# BQ25750.net
KiCad netlist of a schematic drawn in Altium Designer
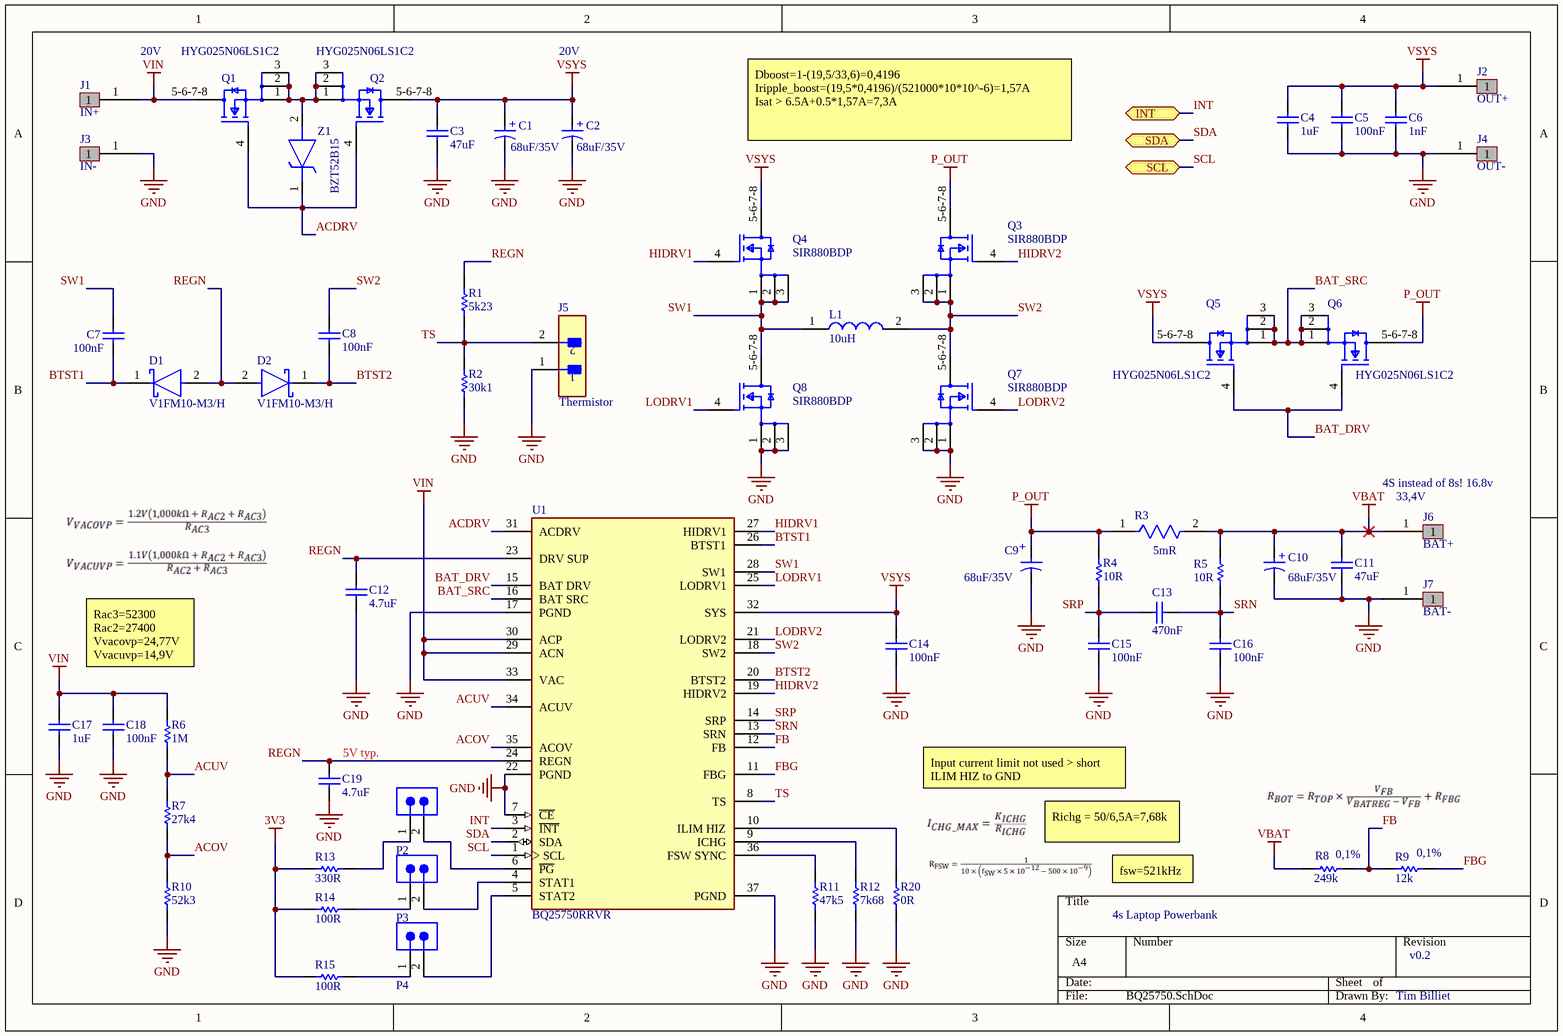
[diagram p0: BQ25750.SchDoc]

(export (version "E")
  (design (tool "Eeschema 10.0.6"))
  (components
    (comp (ref "C1")
      (value "68uF/35V")
      (footprint "Wurth D6.3x7.7mm")
      (fields (field (name "Comment") "Nichicon 68uF/35V Elco"))
      (libsource (lib "Passives") (part "Nichicon 68uF/35V Elco"))
    )
    (comp (ref "C2")
      (value "68uF/35V")
      (footprint "Wurth D6.3x7.7mm")
      (fields (field (name "Comment") "Nichicon 68uF/35V Elco"))
      (libsource (lib "Passives") (part "Nichicon 68uF/35V Elco"))
    )
    (comp (ref "C3")
      (value "47uF")
      (footprint "Wurth 1206 Capacitor")
      (fields (field (name "Comment") "Generic Capacitor 47uF 1206"))
      (libsource (lib "Passives") (part "Generic Capacitor 47uF 1206"))
    )
    (comp (ref "C4")
      (value "1uF")
      (footprint "Wurth 1206 Capacitor")
      (fields (field (name "Comment") "Generic Capacitor 1uF 1206"))
      (libsource (lib "Passives") (part "Generic Capacitor 1uF 1206"))
    )
    (comp (ref "C5")
      (value "100nF")
      (footprint "Wurth 0603 capacitor")
      (fields (field (name "Comment") "Generic Capacitor 100nF 0603"))
      (libsource (lib "Passives") (part "Generic Capacitor 100nF 0603"))
    )
    (comp (ref "C6")
      (value "1nF")
      (footprint "Wurth 0603 capacitor")
      (fields (field (name "Comment") "Generic Capacitor 1nF 0603"))
      (libsource (lib "Passives") (part "Generic Capacitor 1nF 0603"))
    )
    (comp (ref "C7")
      (value "100nF")
      (footprint "Wurth 0603 capacitor")
      (fields (field (name "Comment") "Generic Capacitor 100nF 0603"))
      (libsource (lib "Passives") (part "Generic Capacitor 100nF 0603"))
    )
    (comp (ref "C8")
      (value "100nF")
      (footprint "Wurth 0603 capacitor")
      (fields (field (name "Comment") "Generic Capacitor 100nF 0603"))
      (libsource (lib "Passives") (part "Generic Capacitor 100nF 0603"))
    )
    (comp (ref "C9")
      (value "68uF/35V")
      (footprint "Wurth D6.3x7.7mm")
      (fields (field (name "Comment") "Nichicon 68uF/35V Elco"))
      (libsource (lib "") (part "Nichicon 68uF/35V Elco_1"))
    )
    (comp (ref "C10")
      (value "68uF/35V")
      (footprint "Wurth D6.3x7.7mm")
      (fields (field (name "Comment") "Nichicon 68uF/35V Elco"))
      (libsource (lib "Passives") (part "Nichicon 68uF/35V Elco"))
    )
    (comp (ref "C11")
      (value "47uF")
      (footprint "Wurth 1206 Capacitor")
      (fields (field (name "Comment") "Generic Capacitor 47uF 1206"))
      (libsource (lib "Passives") (part "Generic Capacitor 47uF 1206"))
    )
    (comp (ref "C12")
      (value "4.7uF")
      (footprint "Wurth 0603 capacitor")
      (fields (field (name "Comment") "Generic Capacitor 4.7uF 0603"))
      (libsource (lib "Passives") (part "Generic Capacitor 4.7uF 0603"))
    )
    (comp (ref "C13")
      (value "470nF")
      (footprint "Wurth 0603 capacitor")
      (fields (field (name "Comment") "Generic Capacitor 470nF 0603"))
      (libsource (lib "Passives") (part "Generic Capacitor 470nF 0603"))
    )
    (comp (ref "C14")
      (value "100nF")
      (footprint "Wurth 0603 capacitor")
      (fields (field (name "Comment") "Generic Capacitor 100nF 0603"))
      (libsource (lib "Passives") (part "Generic Capacitor 100nF 0603"))
    )
    (comp (ref "C15")
      (value "100nF")
      (footprint "Wurth 0603 capacitor")
      (fields (field (name "Comment") "Generic Capacitor 100nF 0603"))
      (libsource (lib "Passives") (part "Generic Capacitor 100nF 0603"))
    )
    (comp (ref "C16")
      (value "100nF")
      (footprint "Wurth 0603 capacitor")
      (fields (field (name "Comment") "Generic Capacitor 100nF 0603"))
      (libsource (lib "Passives") (part "Generic Capacitor 100nF 0603"))
    )
    (comp (ref "C17")
      (value "1uF")
      (footprint "Wurth 0603 capacitor")
      (fields (field (name "Comment") "Generic Capacitor 1uF 0603"))
      (libsource (lib "Passives") (part "Generic Capacitor 1uF 0603"))
    )
    (comp (ref "C18")
      (value "100nF")
      (footprint "Wurth 0603 capacitor")
      (fields (field (name "Comment") "Generic Capacitor 100nF 0603"))
      (libsource (lib "Passives") (part "Generic Capacitor 100nF 0603"))
    )
    (comp (ref "C19")
      (value "4.7uF")
      (footprint "Wurth 0603 capacitor")
      (fields (field (name "Comment") "Generic Capacitor 4.7uF 0603"))
      (libsource (lib "Passives") (part "Generic Capacitor 4.7uF 0603"))
    )
    (comp (ref "D1")
      (value "V1FM10-M3/H")
      (footprint "FP-V1FM10-M3-H-MFG")
      (description "1A 100V SMF TRENCH SKY RECT")
      (libsource (lib "Altium Content Vault") (part "1d6ec82d83fb6aee721767c19dac4b9"))
    )
    (comp (ref "D2")
      (value "V1FM10-M3/H")
      (footprint "FP-V1FM10-M3-H-MFG")
      (description "1A 100V SMF TRENCH SKY RECT")
      (libsource (lib "Altium Content Vault") (part "1d6ec82d83fb6aee721767c19dac4b9"))
    )
    (comp (ref "J1") (value "IN+") (footprint "Solder Pad 3X4MM") (libsource (lib "") (part "Solder pad_1")))
    (comp (ref "J2")
      (value "OUT+")
      (footprint "Solder Pad 3X4MM")
      (libsource (lib "Connectors") (part "Solder pad"))
    )
    (comp (ref "J3") (value "IN-") (footprint "Solder Pad 3X4MM") (libsource (lib "") (part "Solder pad_1")))
    (comp (ref "J4")
      (value "OUT-")
      (footprint "Solder Pad 3X4MM")
      (libsource (lib "Connectors") (part "Solder pad"))
    )
    (comp (ref "J5")
      (value "B2B-PH-K(LF)(SN)")
      (footprint "FP-B2B-PH-K_LF_SN-MFG")
      (description "Connector Header Through Hole 2 position 0.079\" (2.00mm)")
      (libsource (lib "Altium Content Vault") (part "3bc925449376181038e59eaffc5286c"))
    )
    (comp (ref "J6")
      (value "BAT+")
      (footprint "Solder Pad 3X4MM")
      (libsource (lib "Connectors") (part "Solder pad"))
    )
    (comp (ref "J7")
      (value "BAT-")
      (footprint "Solder Pad 3X4MM")
      (libsource (lib "Connectors") (part "Solder pad"))
    )
    (comp (ref "L1")
      (value "10uH")
      (footprint "Cjiang 11.5x10mm inductor")
      (fields (field (name "Comment") "Cjiang Inductor 10uH 8A"))
      (libsource (lib "Passives") (part "Cjiang Inductor 10uH 8A"))
    )
    (comp (ref "P2")
      (value "61300211121")
      (footprint "2x1 2.54mm F")
      (description "WR-PHD Pin Header, THT, Vertical, pitch 2.54mm, 1 Row, 2P")
      (fields (field (name "MANUFACTURER") "Wurth Elektronik"))
      (libsource (lib "2.54mm_pin_headers") (part "2P"))
    )
    (comp (ref "P3")
      (value "61300211121")
      (footprint "2x1 2.54mm F")
      (description "WR-PHD Pin Header, THT, Vertical, pitch 2.54mm, 1 Row, 2P")
      (fields (field (name "MANUFACTURER") "Wurth Elektronik"))
      (libsource (lib "2.54mm_pin_headers") (part "2P"))
    )
    (comp (ref "P4")
      (value "61300211121")
      (footprint "2x1 2.54mm F")
      (description "WR-PHD Pin Header, THT, Vertical, pitch 2.54mm, 1 Row, 2P")
      (fields (field (name "MANUFACTURER") "Wurth Elektronik"))
      (libsource (lib "2.54mm_pin_headers") (part "2P"))
    )
    (comp (ref "Q1")
      (value "HYG025N06LS1C2")
      (footprint "Huayi PDFN8L")
      (description "MOSFET N-CH VDS = 60V,ID = 170A, VGS = 20V PDFN8L")
      (libsource (lib "N CHN FET") (part "Huayi HYG025N06LS1C2"))
    )
    (comp (ref "Q2")
      (value "HYG025N06LS1C2")
      (footprint "Huayi PDFN8L")
      (description "MOSFET N-CH VDS = 60V,ID = 170A, VGS = 20V PDFN8L")
      (libsource (lib "N CHN FET") (part "Huayi HYG025N06LS1C2"))
    )
    (comp (ref "Q3")
      (value "SIR880BDP")
      (footprint "Vishay PowerPAKSO-8")
      (description "Mosfet, N-Ch, 80V, 70.6A, 150Degc, 71.4W Rohs Compliant: Yes ¦Vishay SIR880BDP-T1-RE3")
      (fields
        (field (name "MANUFACTURER") "Vishay")
        (field (name "MANUFACTURER PART NUMBER") "SIR880BDP-T1-RE3")
      )
      (libsource (lib "N_CHN_FET") (part "Vishay SIR880BDP"))
    )
    (comp (ref "Q4")
      (value "SIR880BDP")
      (footprint "Vishay PowerPAKSO-8")
      (description "Mosfet, N-Ch, 80V, 70.6A, 150Degc, 71.4W Rohs Compliant: Yes ¦Vishay SIR880BDP-T1-RE3")
      (fields
        (field (name "MANUFACTURER") "Vishay")
        (field (name "MANUFACTURER PART NUMBER") "SIR880BDP-T1-RE3")
      )
      (libsource (lib "N_CHN_FET") (part "Vishay SIR880BDP"))
    )
    (comp (ref "Q5")
      (value "HYG025N06LS1C2")
      (footprint "Huayi PDFN8L")
      (description "MOSFET N-CH VDS = 60V,ID = 170A, VGS = 20V PDFN8L")
      (libsource (lib "N CHN FET") (part "Huayi HYG025N06LS1C2"))
    )
    (comp (ref "Q6")
      (value "HYG025N06LS1C2")
      (footprint "Huayi PDFN8L")
      (description "MOSFET N-CH VDS = 60V,ID = 170A, VGS = 20V PDFN8L")
      (libsource (lib "N CHN FET") (part "Huayi HYG025N06LS1C2"))
    )
    (comp (ref "Q7")
      (value "SIR880BDP")
      (footprint "Vishay PowerPAKSO-8")
      (description "Mosfet, N-Ch, 80V, 70.6A, 150Degc, 71.4W Rohs Compliant: Yes ¦Vishay SIR880BDP-T1-RE3")
      (fields
        (field (name "MANUFACTURER") "Vishay")
        (field (name "MANUFACTURER PART NUMBER") "SIR880BDP-T1-RE3")
      )
      (libsource (lib "N_CHN_FET") (part "Vishay SIR880BDP"))
    )
    (comp (ref "Q8")
      (value "SIR880BDP")
      (footprint "Vishay PowerPAKSO-8")
      (description "Mosfet, N-Ch, 80V, 70.6A, 150Degc, 71.4W Rohs Compliant: Yes ¦Vishay SIR880BDP-T1-RE3")
      (fields
        (field (name "MANUFACTURER") "Vishay")
        (field (name "MANUFACTURER PART NUMBER") "SIR880BDP-T1-RE3")
      )
      (libsource (lib "N_CHN_FET") (part "Vishay SIR880BDP"))
    )
    (comp (ref "R1")
      (value "5k23")
      (footprint "Wurth 0603 Resistor")
      (fields (field (name "Comment") "Generic Resistor 5k23 0603"))
      (libsource (lib "Passives") (part "Generic Resistor 5k23 0603"))
    )
    (comp (ref "R2")
      (value "30k1")
      (footprint "Wurth 0603 Resistor")
      (fields (field (name "Comment") "Generic Resistor 30k1 0603"))
      (libsource (lib "Passives") (part "Generic Resistor 30k1 0603"))
    )
    (comp (ref "R3")
      (value "ERJ-M1WSF5M0U")
      (footprint "FP-ERJM1WS-MFG")
      (description "RES 0.005 OHM 1% 1W 2512")
      (fields (field (name "RESISTANCE") "5mR") (field (name "TOLERANCE") "1%"))
      (libsource (lib "Altium Content Vault") (part "8db39607336c341a927600551d01821"))
    )
    (comp (ref "R4")
      (value "10R")
      (footprint "Wurth 0603 Resistor")
      (fields (field (name "Comment") "Generic Resistor 10R 0603"))
      (libsource (lib "Passives") (part "Generic Resistor 10R 0603"))
    )
    (comp (ref "R5")
      (value "10R")
      (footprint "Wurth 0603 Resistor")
      (fields (field (name "Comment") "Generic Resistor 10R 0603"))
      (libsource (lib "Passives") (part "Generic Resistor 10R 0603"))
    )
    (comp (ref "R6")
      (value "1M")
      (footprint "Wurth 0603 Resistor")
      (fields (field (name "Comment") "Generic Resistor 1M 0603"))
      (libsource (lib "Passives") (part "Generic Resistor 1M 0603"))
    )
    (comp (ref "R7")
      (value "27k4")
      (footprint "Wurth 0603 Resistor")
      (fields (field (name "Comment") "Generic Resistor 27k4 0603"))
      (libsource (lib "Passives") (part "Generic Resistor 27k4 0603"))
    )
    (comp (ref "R8")
      (value "249k")
      (footprint "Wurth 0603 Resistor")
      (fields (field (name "Comment") "Generic Resistor 249k 0603"))
      (libsource (lib "Passives") (part "Generic Resistor 249k 0603"))
    )
    (comp (ref "R9")
      (value "12k")
      (footprint "Wurth 0603 Resistor")
      (fields (field (name "Comment") "Generic Resistor 12k 0603"))
      (libsource (lib "Passives") (part "Generic Resistor 12k 0603"))
    )
    (comp (ref "R10")
      (value "52k3")
      (footprint "Wurth 0603 Resistor")
      (fields (field (name "Comment") "Generic Resistor 52k3 0603"))
      (libsource (lib "Passives") (part "Generic Resistor 52k3 0603"))
    )
    (comp (ref "R11")
      (value "47k5")
      (footprint "Wurth 0603 Resistor")
      (fields (field (name "Comment") "Generic Resistor 47k5 0603"))
      (libsource (lib "Passives") (part "Generic Resistor 47k5 0603"))
    )
    (comp (ref "R12")
      (value "7k68")
      (footprint "Wurth 0603 Resistor")
      (fields (field (name "Comment") "Generic Resistor 7k68 0603"))
      (libsource (lib "Passives") (part "Generic Resistor 7k68 0603"))
    )
    (comp (ref "R13")
      (value "330R")
      (footprint "Wurth 0603 Resistor")
      (fields (field (name "Comment") "Generic Resistor 330R 0603"))
      (libsource (lib "Passives") (part "Generic Resistor 330R 0603"))
    )
    (comp (ref "R14")
      (value "100R")
      (footprint "Wurth 0603 Resistor")
      (fields (field (name "Comment") "Generic Resistor 100R 0603"))
      (libsource (lib "Passives") (part "Generic Resistor 100R 0603"))
    )
    (comp (ref "R15")
      (value "100R")
      (footprint "Wurth 0603 Resistor")
      (fields (field (name "Comment") "Generic Resistor 100R 0603"))
      (libsource (lib "Passives") (part "Generic Resistor 100R 0603"))
    )
    (comp (ref "R20")
      (value "0R")
      (footprint "Wurth 0603 Resistor")
      (fields (field (name "Comment") "Generic Resistor 0R 0603"))
      (libsource (lib "Passives") (part "Generic Resistor 0R 0603"))
    )
    (comp (ref "U1")
      (value "BQ25750RRVR")
      (footprint "FP-RRV0036A-MFG")
      (libsource (lib "Altium Content Vault") (part "ac6e1909637b173ef10636b2c9122d3"))
    )
    (comp (ref "Z1")
      (value "BZT52B15")
      (footprint "Yongyutai SOD-123")
      (description "Zener Diode")
      (fields
        (field (name "MANUFACTURER_PART_NUMBER") "BZT52B15-E3-18")
        (field (name "MOUSER PART NUMBER") "78-BZT52B15-E3-18")
      )
      (libsource (lib "Diodes") (part "BZT52B15"))
    )
  )
  (nets
    (net (code "1") (name "/ACDRV") (class "Default")
      (node (ref "Q1") (pin "4") (pinfunction "G_4") (pintype "passive"))
      (node (ref "Q2") (pin "4") (pinfunction "G_4") (pintype "passive"))
      (node (ref "U1") (pin "31") (pinfunction "ACDRV_31") (pintype "passive"))
      (node (ref "Z1") (pin "1") (pinfunction "K_1") (pintype "passive"))
    )
    (net (code "2") (name "/ACOV") (class "Default")
      (node (ref "R10") (pin "2") (pinfunction "2_2") (pintype "passive"))
      (node (ref "R7") (pin "1") (pinfunction "1_1") (pintype "passive"))
      (node (ref "U1") (pin "35") (pinfunction "ACOV_35") (pintype "passive"))
    )
    (net (code "3") (name "/ACUV") (class "Default")
      (node (ref "R6") (pin "1") (pinfunction "1_1") (pintype "passive"))
      (node (ref "R7") (pin "2") (pinfunction "2_2") (pintype "passive"))
      (node (ref "U1") (pin "34") (pinfunction "ACUV_34") (pintype "passive"))
    )
    (net (code "4") (name "/BAT_DRV") (class "Default")
      (node (ref "Q5") (pin "4") (pinfunction "G_4") (pintype "passive"))
      (node (ref "Q6") (pin "4") (pinfunction "G_4") (pintype "passive"))
      (node (ref "U1") (pin "15") (pinfunction "BAT_DRV_15") (pintype "passive"))
    )
    (net (code "5") (name "/BAT_SRC") (class "Default")
      (node (ref "Q5") (pin "1") (pinfunction "S_1") (pintype "passive"))
      (node (ref "Q5") (pin "2") (pinfunction "S_2") (pintype "passive"))
      (node (ref "Q5") (pin "3") (pinfunction "S_3") (pintype "passive"))
      (node (ref "Q6") (pin "1") (pinfunction "S_1") (pintype "passive"))
      (node (ref "Q6") (pin "2") (pinfunction "S_2") (pintype "passive"))
      (node (ref "Q6") (pin "3") (pinfunction "S_3") (pintype "passive"))
      (node (ref "U1") (pin "16") (pinfunction "BAT_SRC_16") (pintype "passive"))
    )
    (net (code "6") (name "/BTST1") (class "Default")
      (node (ref "C7") (pin "1") (pinfunction "1_1") (pintype "passive"))
      (node (ref "D1") (pin "1") (pinfunction "C_1") (pintype "passive"))
      (node (ref "U1") (pin "26") (pinfunction "BTST1_26") (pintype "passive"))
    )
    (net (code "7") (name "/BTST2") (class "Default")
      (node (ref "C8") (pin "1") (pinfunction "1_1") (pintype "passive"))
      (node (ref "D2") (pin "1") (pinfunction "C_1") (pintype "passive"))
      (node (ref "U1") (pin "20") (pinfunction "BTST2_20") (pintype "passive"))
    )
    (net (code "8") (name "/FB") (class "Default")
      (node (ref "R8") (pin "1") (pinfunction "1_1") (pintype "passive"))
      (node (ref "R9") (pin "1") (pinfunction "1_1") (pintype "passive"))
      (node (ref "U1") (pin "12") (pinfunction "FB_12") (pintype "passive"))
    )
    (net (code "9") (name "/FBG") (class "Default")
      (node (ref "R9") (pin "2") (pinfunction "2_2") (pintype "passive"))
      (node (ref "U1") (pin "11") (pinfunction "FBG_11") (pintype "passive"))
    )
    (net (code "10") (name "/HIDRV1") (class "Default")
      (node (ref "Q4") (pin "4") (pinfunction "G_4") (pintype "passive"))
      (node (ref "U1") (pin "27") (pinfunction "HIDRV1_27") (pintype "passive"))
    )
    (net (code "11") (name "/HIDRV2") (class "Default")
      (node (ref "Q3") (pin "4") (pinfunction "G_4") (pintype "passive"))
      (node (ref "U1") (pin "19") (pinfunction "HIDRV2_19") (pintype "passive"))
    )
    (net (code "12") (name "/INT") (class "Default")
      (node (ref "U1") (pin "3") (pinfunction "~{INT}_3") (pintype "input"))
    )
    (net (code "13") (name "/LODRV1") (class "Default")
      (node (ref "Q8") (pin "4") (pinfunction "G_4") (pintype "passive"))
      (node (ref "U1") (pin "25") (pinfunction "LODRV1_25") (pintype "passive"))
    )
    (net (code "14") (name "/LODRV2") (class "Default")
      (node (ref "Q7") (pin "4") (pinfunction "G_4") (pintype "passive"))
      (node (ref "U1") (pin "21") (pinfunction "LODRV2_21") (pintype "passive"))
    )
    (net (code "15") (name "/REGN") (class "Default")
      (node (ref "C12") (pin "2") (pinfunction "2_2") (pintype "passive"))
      (node (ref "C19") (pin "2") (pinfunction "2_2") (pintype "passive"))
      (node (ref "D1") (pin "2") (pinfunction "A_2") (pintype "passive"))
      (node (ref "D2") (pin "2") (pinfunction "A_2") (pintype "passive"))
      (node (ref "R1") (pin "2") (pinfunction "2_2") (pintype "passive"))
      (node (ref "U1") (pin "23") (pinfunction "DRV_SUP_23") (pintype "passive"))
      (node (ref "U1") (pin "24") (pinfunction "REGN_24") (pintype "passive"))
    )
    (net (code "16") (name "/SCL") (class "Default")
      (node (ref "U1") (pin "1") (pinfunction "SCL_1") (pintype "input"))
    )
    (net (code "17") (name "/SDA") (class "Default")
      (node (ref "U1") (pin "2") (pinfunction "SDA_2") (pintype "bidirectional"))
    )
    (net (code "18") (name "/SRN") (class "Default")
      (node (ref "C13") (pin "2") (pinfunction "2_2") (pintype "passive"))
      (node (ref "C16") (pin "2") (pinfunction "2_2") (pintype "passive"))
      (node (ref "R5") (pin "1") (pinfunction "1_1") (pintype "passive"))
      (node (ref "U1") (pin "13") (pinfunction "SRN_13") (pintype "passive"))
    )
    (net (code "19") (name "/SRP") (class "Default")
      (node (ref "C13") (pin "1") (pinfunction "1_1") (pintype "passive"))
      (node (ref "C15") (pin "1") (pinfunction "1_1") (pintype "passive"))
      (node (ref "R4") (pin "1") (pinfunction "1_1") (pintype "passive"))
      (node (ref "U1") (pin "14") (pinfunction "SRP_14") (pintype "passive"))
    )
    (net (code "20") (name "/SW1") (class "Default")
      (node (ref "C7") (pin "2") (pinfunction "2_2") (pintype "passive"))
      (node (ref "L1") (pin "1") (pinfunction "1_1") (pintype "passive"))
      (node (ref "Q4") (pin "1") (pinfunction "S_1") (pintype "passive"))
      (node (ref "Q4") (pin "2") (pinfunction "S_2") (pintype "passive"))
      (node (ref "Q4") (pin "3") (pinfunction "S_3") (pintype "passive"))
      (node (ref "Q8") (pin "5-6-7-8") (pinfunction "D_5-6-7-8") (pintype "passive"))
      (node (ref "U1") (pin "28") (pinfunction "SW1_28") (pintype "passive"))
    )
    (net (code "21") (name "/SW2") (class "Default")
      (node (ref "C8") (pin "2") (pinfunction "2_2") (pintype "passive"))
      (node (ref "L1") (pin "2") (pinfunction "2_2") (pintype "passive"))
      (node (ref "Q3") (pin "1") (pinfunction "S_1") (pintype "passive"))
      (node (ref "Q3") (pin "2") (pinfunction "S_2") (pintype "passive"))
      (node (ref "Q3") (pin "3") (pinfunction "S_3") (pintype "passive"))
      (node (ref "Q7") (pin "5-6-7-8") (pinfunction "D_5-6-7-8") (pintype "passive"))
      (node (ref "U1") (pin "18") (pinfunction "SW2_18") (pintype "passive"))
    )
    (net (code "22") (name "/TS") (class "Default")
      (node (ref "J5") (pin "2") (pinfunction "2_2") (pintype "passive"))
      (node (ref "R1") (pin "1") (pinfunction "1_1") (pintype "passive"))
      (node (ref "R2") (pin "2") (pinfunction "2_2") (pintype "passive"))
      (node (ref "U1") (pin "8") (pinfunction "TS_8") (pintype "passive"))
    )
    (net (code "23") (name "3V3") (class "Default")
      (node (ref "R13") (pin "1") (pinfunction "1_1") (pintype "passive"))
      (node (ref "R14") (pin "1") (pinfunction "1_1") (pintype "passive"))
      (node (ref "R15") (pin "1") (pinfunction "1_1") (pintype "passive"))
    )
    (net (code "24") (name "GND") (class "Default")
      (node (ref "C1") (pin "2") (pinfunction "N_2") (pintype "passive"))
      (node (ref "C10") (pin "2") (pinfunction "N_2") (pintype "passive"))
      (node (ref "C11") (pin "1") (pinfunction "1_1") (pintype "passive"))
      (node (ref "C12") (pin "1") (pinfunction "1_1") (pintype "passive"))
      (node (ref "C14") (pin "1") (pinfunction "1_1") (pintype "passive"))
      (node (ref "C15") (pin "2") (pinfunction "2_2") (pintype "passive"))
      (node (ref "C16") (pin "1") (pinfunction "1_1") (pintype "passive"))
      (node (ref "C17") (pin "1") (pinfunction "1_1") (pintype "passive"))
      (node (ref "C18") (pin "1") (pinfunction "1_1") (pintype "passive"))
      (node (ref "C19") (pin "1") (pinfunction "1_1") (pintype "passive"))
      (node (ref "C2") (pin "2") (pinfunction "N_2") (pintype "passive"))
      (node (ref "C3") (pin "1") (pinfunction "1_1") (pintype "passive"))
      (node (ref "C4") (pin "1") (pinfunction "1_1") (pintype "passive"))
      (node (ref "C5") (pin "1") (pinfunction "1_1") (pintype "passive"))
      (node (ref "C6") (pin "1") (pinfunction "1_1") (pintype "passive"))
      (node (ref "C9") (pin "2") (pinfunction "N_2") (pintype "passive"))
      (node (ref "J3") (pin "1") (pinfunction "1_1") (pintype "passive"))
      (node (ref "J4") (pin "1") (pinfunction "1_1") (pintype "passive"))
      (node (ref "J5") (pin "1") (pinfunction "1_1") (pintype "passive"))
      (node (ref "J7") (pin "1") (pinfunction "1_1") (pintype "passive"))
      (node (ref "Q7") (pin "1") (pinfunction "S_1") (pintype "passive"))
      (node (ref "Q7") (pin "2") (pinfunction "S_2") (pintype "passive"))
      (node (ref "Q7") (pin "3") (pinfunction "S_3") (pintype "passive"))
      (node (ref "Q8") (pin "1") (pinfunction "S_1") (pintype "passive"))
      (node (ref "Q8") (pin "2") (pinfunction "S_2") (pintype "passive"))
      (node (ref "Q8") (pin "3") (pinfunction "S_3") (pintype "passive"))
      (node (ref "R10") (pin "1") (pinfunction "1_1") (pintype "passive"))
      (node (ref "R11") (pin "1") (pinfunction "1_1") (pintype "passive"))
      (node (ref "R12") (pin "2") (pinfunction "2_2") (pintype "passive"))
      (node (ref "R2") (pin "1") (pinfunction "1_1") (pintype "passive"))
      (node (ref "R20") (pin "1") (pinfunction "1_1") (pintype "passive"))
      (node (ref "U1") (pin "17") (pinfunction "PGND_17") (pintype "power_in"))
      (node (ref "U1") (pin "22") (pinfunction "PGND_22") (pintype "power_in"))
      (node (ref "U1") (pin "37") (pinfunction "PGND_37") (pintype "power_in"))
      (node (ref "U1") (pin "7") (pinfunction "~{CE}_7") (pintype "input"))
    )
    (net (code "25") (name "Net-(P2-Pad1)") (class "Default")
      (node (ref "P2") (pin "1") (pinfunction "1_1") (pintype "passive"))
      (node (ref "R13") (pin "2") (pinfunction "2_2") (pintype "passive"))
    )
    (net (code "26") (name "Net-(P3-Pad1)") (class "Default")
      (node (ref "P3") (pin "1") (pinfunction "1_1") (pintype "passive"))
      (node (ref "R14") (pin "2") (pinfunction "2_2") (pintype "passive"))
    )
    (net (code "27") (name "Net-(P4-Pad1)") (class "Default")
      (node (ref "P4") (pin "1") (pinfunction "1_1") (pintype "passive"))
      (node (ref "R15") (pin "2") (pinfunction "2_2") (pintype "passive"))
    )
    (net (code "28") (name "Net-(U1-FSW_SYNC)") (class "Default")
      (node (ref "R11") (pin "2") (pinfunction "2_2") (pintype "passive"))
      (node (ref "U1") (pin "36") (pinfunction "FSW_SYNC_36") (pintype "passive"))
    )
    (net (code "29") (name "Net-(U1-ICHG)") (class "Default")
      (node (ref "R12") (pin "1") (pinfunction "1_1") (pintype "passive"))
      (node (ref "U1") (pin "9") (pinfunction "ICHG_9") (pintype "passive"))
    )
    (net (code "30") (name "Net-(U1-ILIM_HIZ)") (class "Default")
      (node (ref "R20") (pin "2") (pinfunction "2_2") (pintype "passive"))
      (node (ref "U1") (pin "10") (pinfunction "ILIM_HIZ_10") (pintype "passive"))
    )
    (net (code "31") (name "Net-(U1-STAT1)") (class "Default")
      (node (ref "P3") (pin "2") (pinfunction "2_2") (pintype "passive"))
      (node (ref "U1") (pin "4") (pinfunction "STAT1_4") (pintype "passive"))
    )
    (net (code "32") (name "Net-(U1-STAT2)") (class "Default")
      (node (ref "P4") (pin "2") (pinfunction "2_2") (pintype "passive"))
      (node (ref "U1") (pin "5") (pinfunction "STAT2_5") (pintype "passive"))
    )
    (net (code "33") (name "Net-(U1-~{PG})") (class "Default")
      (node (ref "P2") (pin "2") (pinfunction "2_2") (pintype "passive"))
      (node (ref "U1") (pin "6") (pinfunction "~{PG}_6") (pintype "open_collector"))
    )
    (net (code "34") (name "Net-(Z1-A)") (class "Default")
      (node (ref "Q1") (pin "1") (pinfunction "S_1") (pintype "passive"))
      (node (ref "Q1") (pin "2") (pinfunction "S_2") (pintype "passive"))
      (node (ref "Q1") (pin "3") (pinfunction "S_3") (pintype "passive"))
      (node (ref "Q2") (pin "1") (pinfunction "S_1") (pintype "passive"))
      (node (ref "Q2") (pin "2") (pinfunction "S_2") (pintype "passive"))
      (node (ref "Q2") (pin "3") (pinfunction "S_3") (pintype "passive"))
      (node (ref "Z1") (pin "2") (pinfunction "A_2") (pintype "passive"))
    )
    (net (code "35") (name "P_OUT") (class "Default")
      (node (ref "C9") (pin "1") (pinfunction "P_1") (pintype "passive"))
      (node (ref "Q3") (pin "5-6-7-8") (pinfunction "D_5-6-7-8") (pintype "passive"))
      (node (ref "Q6") (pin "5-6-7-8") (pinfunction "D_5-6-7-8") (pintype "passive"))
      (node (ref "R3") (pin "1") (pinfunction "1_1") (pintype "passive"))
      (node (ref "R4") (pin "2") (pinfunction "2_2") (pintype "passive"))
    )
    (net (code "36") (name "VBAT") (class "Default")
      (node (ref "C10") (pin "1") (pinfunction "P_1") (pintype "passive"))
      (node (ref "C11") (pin "2") (pinfunction "2_2") (pintype "passive"))
      (node (ref "J6") (pin "1") (pinfunction "1_1") (pintype "passive"))
      (node (ref "R3") (pin "2") (pinfunction "2_2") (pintype "passive"))
      (node (ref "R5") (pin "2") (pinfunction "2_2") (pintype "passive"))
      (node (ref "R8") (pin "2") (pinfunction "2_2") (pintype "passive"))
    )
    (net (code "37") (name "VIN") (class "Default")
      (node (ref "C17") (pin "2") (pinfunction "2_2") (pintype "passive"))
      (node (ref "C18") (pin "2") (pinfunction "2_2") (pintype "passive"))
      (node (ref "J1") (pin "1") (pinfunction "1_1") (pintype "passive"))
      (node (ref "Q1") (pin "5-6-7-8") (pinfunction "D_5-6-7-8") (pintype "passive"))
      (node (ref "R6") (pin "2") (pinfunction "2_2") (pintype "passive"))
      (node (ref "U1") (pin "29") (pinfunction "ACN_29") (pintype "passive"))
      (node (ref "U1") (pin "30") (pinfunction "ACP_30") (pintype "passive"))
      (node (ref "U1") (pin "33") (pinfunction "VAC_33") (pintype "passive"))
    )
    (net (code "38") (name "VSYS") (class "Default")
      (node (ref "C1") (pin "1") (pinfunction "P_1") (pintype "passive"))
      (node (ref "C14") (pin "2") (pinfunction "2_2") (pintype "passive"))
      (node (ref "C2") (pin "1") (pinfunction "P_1") (pintype "passive"))
      (node (ref "C3") (pin "2") (pinfunction "2_2") (pintype "passive"))
      (node (ref "C4") (pin "2") (pinfunction "2_2") (pintype "passive"))
      (node (ref "C5") (pin "2") (pinfunction "2_2") (pintype "passive"))
      (node (ref "C6") (pin "2") (pinfunction "2_2") (pintype "passive"))
      (node (ref "J2") (pin "1") (pinfunction "1_1") (pintype "passive"))
      (node (ref "Q2") (pin "5-6-7-8") (pinfunction "D_5-6-7-8") (pintype "passive"))
      (node (ref "Q4") (pin "5-6-7-8") (pinfunction "D_5-6-7-8") (pintype "passive"))
      (node (ref "Q5") (pin "5-6-7-8") (pinfunction "D_5-6-7-8") (pintype "passive"))
      (node (ref "U1") (pin "32") (pinfunction "SYS_32") (pintype "passive"))
    )
  )
)
